# BasculeD.net
KiCad netlist of a schematic drawn in EAGLE
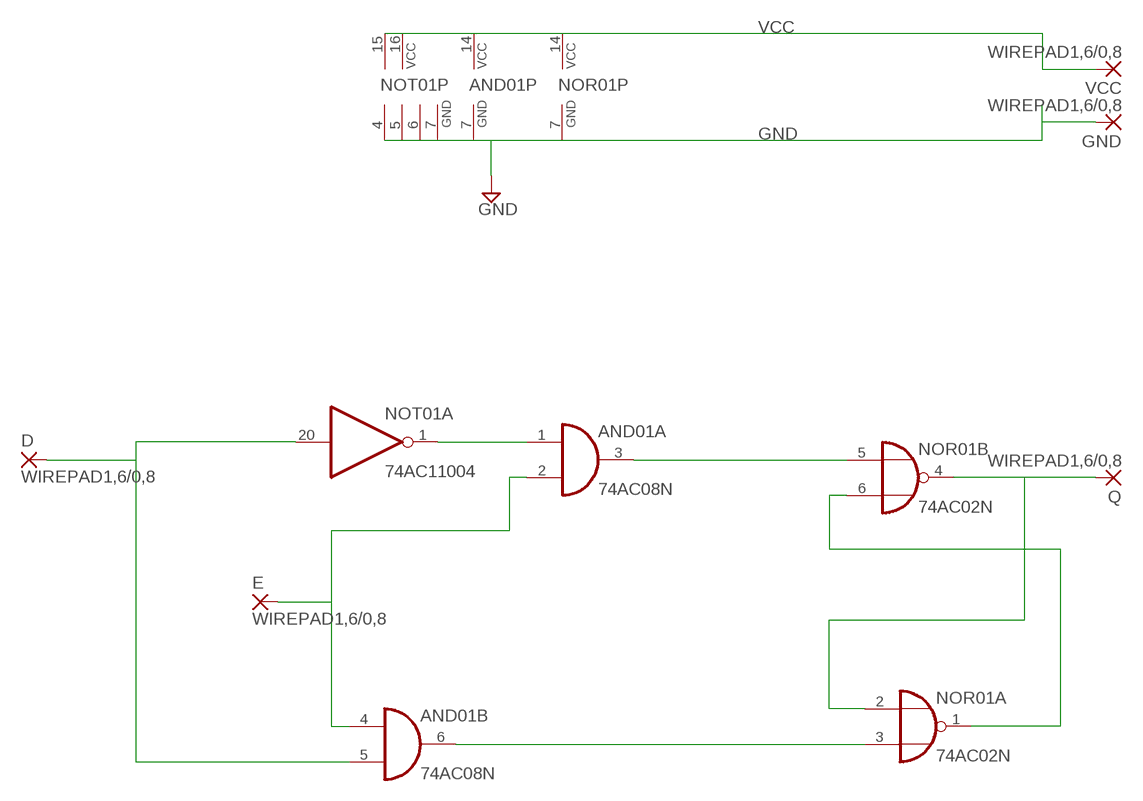
[diagram p0: schematic, sheet 1]

(export (version "E")
  (design (tool "Eeschema 10.0.6"))
  (components
    (comp (ref "AND01")
      (value "74AC08N")
      (footprint "eagle-import:DIL14")
      (libsource (lib "eagle-import") (part "7408NAC"))
    )
    (comp (ref "D")
      (value "WIREPAD1,6/0,8")
      (footprint "eagle-import:1,6_0,8")
      (libsource (lib "eagle-import") (part "WIREPAD1,6/0,8"))
    )
    (comp (ref "E")
      (value "WIREPAD1,6/0,8")
      (footprint "eagle-import:1,6_0,8")
      (libsource (lib "eagle-import") (part "WIREPAD1,6/0,8"))
    )
    (comp (ref "GND")
      (value "WIREPAD1,6/0,8")
      (footprint "eagle-import:1,6_0,8")
      (libsource (lib "eagle-import") (part "WIREPAD1,6/0,8"))
    )
    (comp (ref "NOR01")
      (value "74AC02N")
      (footprint "eagle-import:DIL14")
      (libsource (lib "eagle-import") (part "7402NAC"))
    )
    (comp (ref "NOT01")
      (value "74AC11004")
      (footprint "eagle-import:DIL20")
      (libsource (lib "eagle-import") (part "74AC11004"))
    )
    (comp (ref "Q")
      (value "WIREPAD1,6/0,8")
      (footprint "eagle-import:1,6_0,8")
      (libsource (lib "eagle-import") (part "WIREPAD1,6/0,8"))
    )
    (comp (ref "VCC")
      (value "WIREPAD1,6/0,8")
      (footprint "eagle-import:1,6_0,8")
      (libsource (lib "eagle-import") (part "WIREPAD1,6/0,8"))
    )
  )
  (nets
    (net (code "1") (name "/VCC") (class "Default")
      (node (ref "AND01") (pin "14") (pinfunction "VCC_14") (pintype "power_in"))
      (node (ref "NOR01") (pin "14") (pinfunction "VCC_14") (pintype "power_in"))
      (node (ref "NOT01") (pin "15") (pinfunction "VCC_15") (pintype "power_in"))
      (node (ref "NOT01") (pin "16") (pinfunction "VCC_16") (pintype "power_in"))
      (node (ref "VCC") (pin "1") (pinfunction "P_1") (pintype "passive"))
    )
    (net (code "2") (name "GND") (class "Default")
      (node (ref "AND01") (pin "7") (pinfunction "GND_7") (pintype "power_in"))
      (node (ref "GND") (pin "1") (pinfunction "P_1") (pintype "passive"))
      (node (ref "NOR01") (pin "7") (pinfunction "GND_7") (pintype "power_in"))
      (node (ref "NOT01") (pin "4") (pinfunction "GND_4") (pintype "power_in"))
      (node (ref "NOT01") (pin "5") (pinfunction "GND_5") (pintype "power_in"))
      (node (ref "NOT01") (pin "6") (pinfunction "GND_6") (pintype "power_in"))
      (node (ref "NOT01") (pin "7") (pinfunction "GND_7") (pintype "power_in"))
    )
    (net (code "3") (name "Net-(AND01A-I0)") (class "Default")
      (node (ref "AND01") (pin "1") (pinfunction "I0_1") (pintype "input"))
      (node (ref "NOT01") (pin "1") (pinfunction "O_1") (pintype "output"))
    )
    (net (code "4") (name "Net-(AND01A-I1)") (class "Default")
      (node (ref "AND01") (pin "2") (pinfunction "I1_2") (pintype "input"))
      (node (ref "AND01") (pin "4") (pinfunction "I0_4") (pintype "input"))
      (node (ref "E") (pin "1") (pinfunction "P_1") (pintype "passive"))
    )
    (net (code "5") (name "Net-(AND01A-O)") (class "Default")
      (node (ref "AND01") (pin "3") (pinfunction "O_3") (pintype "output"))
      (node (ref "NOR01") (pin "5") (pinfunction "I0_5") (pintype "input"))
    )
    (net (code "6") (name "Net-(AND01B-I1)") (class "Default")
      (node (ref "AND01") (pin "5") (pinfunction "I1_5") (pintype "input"))
      (node (ref "D") (pin "1") (pinfunction "P_1") (pintype "passive"))
      (node (ref "NOT01") (pin "20") (pinfunction "I_20") (pintype "input"))
    )
    (net (code "7") (name "Net-(AND01B-O)") (class "Default")
      (node (ref "AND01") (pin "6") (pinfunction "O_6") (pintype "output"))
      (node (ref "NOR01") (pin "3") (pinfunction "I1_3") (pintype "input"))
    )
    (net (code "8") (name "Net-(NOR01A-I0)") (class "Default")
      (node (ref "NOR01") (pin "2") (pinfunction "I0_2") (pintype "input"))
      (node (ref "NOR01") (pin "4") (pinfunction "O_4") (pintype "output"))
      (node (ref "Q") (pin "1") (pinfunction "P_1") (pintype "passive"))
    )
    (net (code "9") (name "Net-(NOR01A-O)") (class "Default")
      (node (ref "NOR01") (pin "1") (pinfunction "O_1") (pintype "output"))
      (node (ref "NOR01") (pin "6") (pinfunction "I1_6") (pintype "input"))
    )
  )
)
